# MiniPDB.net
KiCad netlist of a schematic drawn in EAGLE
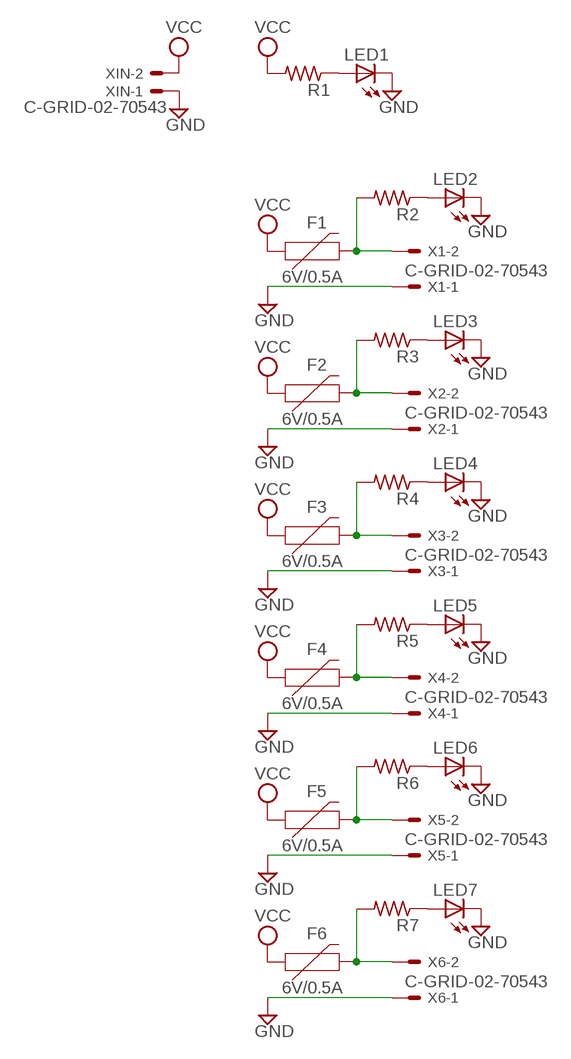
[diagram p0: schematic, sheet 1]

(export (version "E")
  (design (tool "Eeschema 10.0.6"))
  (components
    (comp (ref "F1")
      (value "6V/0.5A")
      (footprint "eagle-import:1206")
      (libsource (lib "eagle-import") (part "PPTC_HALF-AMP"))
    )
    (comp (ref "F2")
      (value "6V/0.5A")
      (footprint "eagle-import:1206")
      (libsource (lib "eagle-import") (part "PPTC_HALF-AMP"))
    )
    (comp (ref "F3")
      (value "6V/0.5A")
      (footprint "eagle-import:1206")
      (libsource (lib "eagle-import") (part "PPTC_HALF-AMP"))
    )
    (comp (ref "F4")
      (value "6V/0.5A")
      (footprint "eagle-import:1206")
      (libsource (lib "eagle-import") (part "PPTC_HALF-AMP"))
    )
    (comp (ref "F5")
      (value "6V/0.5A")
      (footprint "eagle-import:1206")
      (libsource (lib "eagle-import") (part "PPTC_HALF-AMP"))
    )
    (comp (ref "F6")
      (value "6V/0.5A")
      (footprint "eagle-import:1206")
      (libsource (lib "eagle-import") (part "PPTC_HALF-AMP"))
    )
    (comp (ref "LED1")
      (value "LEDCHIPLED_1206")
      (footprint "eagle-import:CHIPLED_1206")
      (libsource (lib "eagle-import") (part "LEDCHIPLED_1206"))
    )
    (comp (ref "LED2")
      (value "LEDCHIPLED_1206")
      (footprint "eagle-import:CHIPLED_1206")
      (libsource (lib "eagle-import") (part "LEDCHIPLED_1206"))
    )
    (comp (ref "LED3")
      (value "LEDCHIPLED_1206")
      (footprint "eagle-import:CHIPLED_1206")
      (libsource (lib "eagle-import") (part "LEDCHIPLED_1206"))
    )
    (comp (ref "LED4")
      (value "LEDCHIPLED_1206")
      (footprint "eagle-import:CHIPLED_1206")
      (libsource (lib "eagle-import") (part "LEDCHIPLED_1206"))
    )
    (comp (ref "LED5")
      (value "LEDCHIPLED_1206")
      (footprint "eagle-import:CHIPLED_1206")
      (libsource (lib "eagle-import") (part "LEDCHIPLED_1206"))
    )
    (comp (ref "LED6")
      (value "LEDCHIPLED_1206")
      (footprint "eagle-import:CHIPLED_1206")
      (libsource (lib "eagle-import") (part "LEDCHIPLED_1206"))
    )
    (comp (ref "LED7")
      (value "LEDCHIPLED_1206")
      (footprint "eagle-import:CHIPLED_1206")
      (libsource (lib "eagle-import") (part "LEDCHIPLED_1206"))
    )
    (comp (ref "R1")
      (value "R-US_R1206")
      (footprint "eagle-import:R1206")
      (libsource (lib "eagle-import") (part "R-US_R1206"))
    )
    (comp (ref "R2")
      (value "R-US_R1206")
      (footprint "eagle-import:R1206")
      (libsource (lib "eagle-import") (part "R-US_R1206"))
    )
    (comp (ref "R3")
      (value "R-US_R1206")
      (footprint "eagle-import:R1206")
      (libsource (lib "eagle-import") (part "R-US_R1206"))
    )
    (comp (ref "R4")
      (value "R-US_R1206")
      (footprint "eagle-import:R1206")
      (libsource (lib "eagle-import") (part "R-US_R1206"))
    )
    (comp (ref "R5")
      (value "R-US_R1206")
      (footprint "eagle-import:R1206")
      (libsource (lib "eagle-import") (part "R-US_R1206"))
    )
    (comp (ref "R6")
      (value "R-US_R1206")
      (footprint "eagle-import:R1206")
      (libsource (lib "eagle-import") (part "R-US_R1206"))
    )
    (comp (ref "R7")
      (value "R-US_R1206")
      (footprint "eagle-import:R1206")
      (libsource (lib "eagle-import") (part "R-US_R1206"))
    )
    (comp (ref "X1")
      (value "C-GRID-02-70543")
      (footprint "eagle-import:70543-02")
      (libsource (lib "eagle-import") (part "C-GRID-02-70543"))
    )
    (comp (ref "X2")
      (value "C-GRID-02-70543")
      (footprint "eagle-import:70543-02")
      (libsource (lib "eagle-import") (part "C-GRID-02-70543"))
    )
    (comp (ref "X3")
      (value "C-GRID-02-70543")
      (footprint "eagle-import:70543-02")
      (libsource (lib "eagle-import") (part "C-GRID-02-70543"))
    )
    (comp (ref "X4")
      (value "C-GRID-02-70543")
      (footprint "eagle-import:70543-02")
      (libsource (lib "eagle-import") (part "C-GRID-02-70543"))
    )
    (comp (ref "X5")
      (value "C-GRID-02-70543")
      (footprint "eagle-import:70543-02")
      (libsource (lib "eagle-import") (part "C-GRID-02-70543"))
    )
    (comp (ref "X6")
      (value "C-GRID-02-70543")
      (footprint "eagle-import:70543-02")
      (libsource (lib "eagle-import") (part "C-GRID-02-70543"))
    )
    (comp (ref "XIN")
      (value "C-GRID-02-70543")
      (footprint "eagle-import:70543-02")
      (libsource (lib "eagle-import") (part "C-GRID-02-70543"))
    )
  )
  (nets
    (net (code "1") (name "GND") (class "Default")
      (node (ref "LED1") (pin "C") (pinfunction "C_C") (pintype "passive"))
      (node (ref "LED2") (pin "C") (pinfunction "C_C") (pintype "passive"))
      (node (ref "LED3") (pin "C") (pinfunction "C_C") (pintype "passive"))
      (node (ref "LED4") (pin "C") (pinfunction "C_C") (pintype "passive"))
      (node (ref "LED5") (pin "C") (pinfunction "C_C") (pintype "passive"))
      (node (ref "LED6") (pin "C") (pinfunction "C_C") (pintype "passive"))
      (node (ref "LED7") (pin "C") (pinfunction "C_C") (pintype "passive"))
      (node (ref "X1") (pin "1") (pinfunction "S_1") (pintype "passive"))
      (node (ref "X2") (pin "1") (pinfunction "S_1") (pintype "passive"))
      (node (ref "X3") (pin "1") (pinfunction "S_1") (pintype "passive"))
      (node (ref "X4") (pin "1") (pinfunction "S_1") (pintype "passive"))
      (node (ref "X5") (pin "1") (pinfunction "S_1") (pintype "passive"))
      (node (ref "X6") (pin "1") (pinfunction "S_1") (pintype "passive"))
      (node (ref "XIN") (pin "1") (pinfunction "S_1") (pintype "passive"))
    )
    (net (code "2") (name "Net-(LED1-PadA)") (class "Default")
      (node (ref "LED1") (pin "A") (pinfunction "A_A") (pintype "passive"))
      (node (ref "R1") (pin "1") (pinfunction "1_1") (pintype "passive"))
    )
    (net (code "3") (name "Net-(LED2-PadA)") (class "Default")
      (node (ref "LED2") (pin "A") (pinfunction "A_A") (pintype "passive"))
      (node (ref "R2") (pin "1") (pinfunction "1_1") (pintype "passive"))
    )
    (net (code "4") (name "Net-(LED3-PadA)") (class "Default")
      (node (ref "LED3") (pin "A") (pinfunction "A_A") (pintype "passive"))
      (node (ref "R3") (pin "1") (pinfunction "1_1") (pintype "passive"))
    )
    (net (code "5") (name "Net-(LED4-PadA)") (class "Default")
      (node (ref "LED4") (pin "A") (pinfunction "A_A") (pintype "passive"))
      (node (ref "R4") (pin "1") (pinfunction "1_1") (pintype "passive"))
    )
    (net (code "6") (name "Net-(LED5-PadA)") (class "Default")
      (node (ref "LED5") (pin "A") (pinfunction "A_A") (pintype "passive"))
      (node (ref "R5") (pin "1") (pinfunction "1_1") (pintype "passive"))
    )
    (net (code "7") (name "Net-(LED6-PadA)") (class "Default")
      (node (ref "LED6") (pin "A") (pinfunction "A_A") (pintype "passive"))
      (node (ref "R6") (pin "1") (pinfunction "1_1") (pintype "passive"))
    )
    (net (code "8") (name "Net-(LED7-PadA)") (class "Default")
      (node (ref "LED7") (pin "A") (pinfunction "A_A") (pintype "passive"))
      (node (ref "R7") (pin "1") (pinfunction "1_1") (pintype "passive"))
    )
    (net (code "9") (name "Net-(X1B-S)") (class "Default")
      (node (ref "F1") (pin "2") (pinfunction "2_2") (pintype "bidirectional"))
      (node (ref "R2") (pin "2") (pinfunction "2_2") (pintype "passive"))
      (node (ref "X1") (pin "2") (pinfunction "S_2") (pintype "passive"))
    )
    (net (code "10") (name "Net-(X2B-S)") (class "Default")
      (node (ref "F2") (pin "2") (pinfunction "2_2") (pintype "bidirectional"))
      (node (ref "R3") (pin "2") (pinfunction "2_2") (pintype "passive"))
      (node (ref "X2") (pin "2") (pinfunction "S_2") (pintype "passive"))
    )
    (net (code "11") (name "Net-(X3B-S)") (class "Default")
      (node (ref "F3") (pin "2") (pinfunction "2_2") (pintype "bidirectional"))
      (node (ref "R4") (pin "2") (pinfunction "2_2") (pintype "passive"))
      (node (ref "X3") (pin "2") (pinfunction "S_2") (pintype "passive"))
    )
    (net (code "12") (name "Net-(X4B-S)") (class "Default")
      (node (ref "F4") (pin "2") (pinfunction "2_2") (pintype "bidirectional"))
      (node (ref "R5") (pin "2") (pinfunction "2_2") (pintype "passive"))
      (node (ref "X4") (pin "2") (pinfunction "S_2") (pintype "passive"))
    )
    (net (code "13") (name "Net-(X5B-S)") (class "Default")
      (node (ref "F5") (pin "2") (pinfunction "2_2") (pintype "bidirectional"))
      (node (ref "R6") (pin "2") (pinfunction "2_2") (pintype "passive"))
      (node (ref "X5") (pin "2") (pinfunction "S_2") (pintype "passive"))
    )
    (net (code "14") (name "Net-(X6B-S)") (class "Default")
      (node (ref "F6") (pin "2") (pinfunction "2_2") (pintype "bidirectional"))
      (node (ref "R7") (pin "2") (pinfunction "2_2") (pintype "passive"))
      (node (ref "X6") (pin "2") (pinfunction "S_2") (pintype "passive"))
    )
    (net (code "15") (name "VCC") (class "Default")
      (node (ref "F1") (pin "1") (pinfunction "1_1") (pintype "bidirectional"))
      (node (ref "F2") (pin "1") (pinfunction "1_1") (pintype "bidirectional"))
      (node (ref "F3") (pin "1") (pinfunction "1_1") (pintype "bidirectional"))
      (node (ref "F4") (pin "1") (pinfunction "1_1") (pintype "bidirectional"))
      (node (ref "F5") (pin "1") (pinfunction "1_1") (pintype "bidirectional"))
      (node (ref "F6") (pin "1") (pinfunction "1_1") (pintype "bidirectional"))
      (node (ref "R1") (pin "2") (pinfunction "2_2") (pintype "passive"))
      (node (ref "XIN") (pin "2") (pinfunction "S_2") (pintype "passive"))
    )
  )
)
